# mjGSM.net
KiCad netlist of a schematic drawn in EAGLE
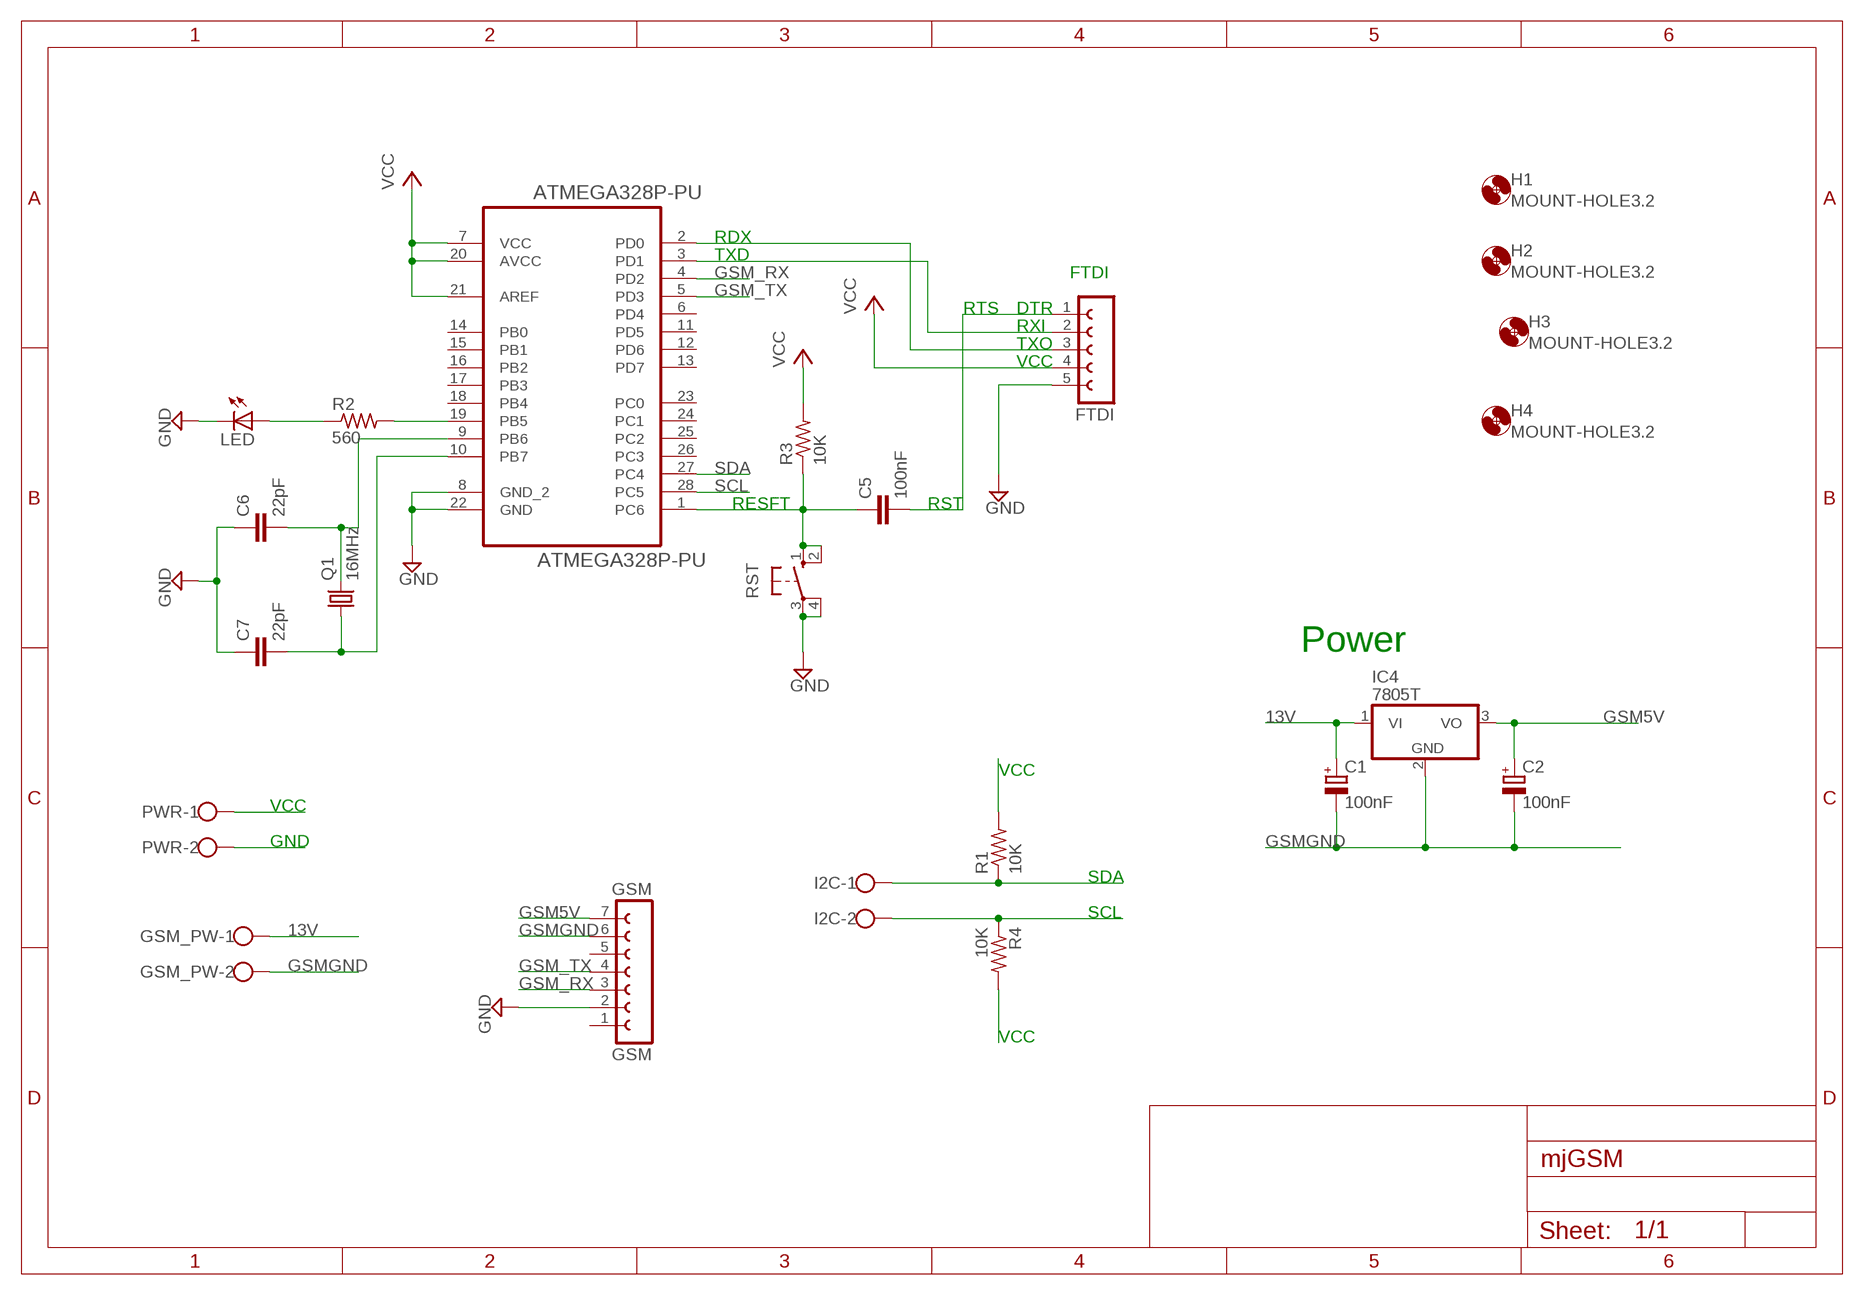
[diagram p0: schematic, sheet 1]

(export (version "E")
  (design (tool "Eeschema 10.0.6"))
  (components
    (comp (ref "ATMEGA328P-PU")
      (value "ATMEGA328P-PU")
      (footprint "eagle-import:DIP254P762X457-28")
      (libsource (lib "eagle-import") (part "ATMEGA328P-PU"))
    )
    (comp (ref "C1")
      (value "100nF")
      (footprint "eagle-import:E2-4")
      (libsource (lib "eagle-import") (part "CPOL-EUE2-4"))
    )
    (comp (ref "C2")
      (value "100nF")
      (footprint "eagle-import:E2-4")
      (libsource (lib "eagle-import") (part "CPOL-EUE2-4"))
    )
    (comp (ref "C5")
      (value "100nF")
      (footprint "eagle-import:C025-024X044")
      (libsource (lib "eagle-import") (part "C-EU025-024X044"))
    )
    (comp (ref "C6")
      (value "22pF")
      (footprint "eagle-import:C025-024X044")
      (libsource (lib "eagle-import") (part "C-EU025-024X044"))
    )
    (comp (ref "C7")
      (value "22pF")
      (footprint "eagle-import:C025-024X044")
      (libsource (lib "eagle-import") (part "C-EU025-024X044"))
    )
    (comp (ref "FTDI")
      (value "FE05-1")
      (footprint "eagle-import:FE05-1")
      (libsource (lib "eagle-import") (part "FE05-1"))
    )
    (comp (ref "GSM")
      (value "GSM")
      (footprint "eagle-import:FE07")
      (libsource (lib "eagle-import") (part "FE07-1"))
    )
    (comp (ref "GSM_PW")
      (value "W237-102")
      (footprint "eagle-import:W237-102")
      (fields (field (name "MPN") "237-102"))
      (libsource (lib "eagle-import") (part "W237-102"))
    )
    (comp (ref "H1")
      (value "MOUNT-HOLE3.2")
      (footprint "eagle-import:3,2")
      (libsource (lib "eagle-import") (part "MOUNT-HOLE3.2"))
    )
    (comp (ref "H2")
      (value "MOUNT-HOLE3.2")
      (footprint "eagle-import:3,2")
      (libsource (lib "eagle-import") (part "MOUNT-HOLE3.2"))
    )
    (comp (ref "H3")
      (value "MOUNT-HOLE3.2")
      (footprint "eagle-import:3,2")
      (libsource (lib "eagle-import") (part "MOUNT-HOLE3.2"))
    )
    (comp (ref "H4")
      (value "MOUNT-HOLE3.2")
      (footprint "eagle-import:3,2")
      (libsource (lib "eagle-import") (part "MOUNT-HOLE3.2"))
    )
    (comp (ref "I2C")
      (value "W237-102")
      (footprint "eagle-import:W237-102")
      (fields (field (name "MPN") "237-102"))
      (libsource (lib "eagle-import") (part "W237-102"))
    )
    (comp (ref "IC4")
      (value "7805T")
      (footprint "eagle-import:TO220H")
      (libsource (lib "eagle-import") (part "78T05"))
    )
    (comp (ref "LED")
      (value "LED3MM")
      (footprint "eagle-import:LED3MM")
      (libsource (lib "eagle-import") (part "LED3MM"))
    )
    (comp (ref "PWR")
      (value "W237-102")
      (footprint "eagle-import:W237-102")
      (fields (field (name "MPN") "237-102") (field (name "SPICEPREFIX") "X"))
      (libsource (lib "eagle-import") (part "W237-102"))
    )
    (comp (ref "Q1")
      (value "16MHz")
      (footprint "eagle-import:HC49_S")
      (libsource (lib "eagle-import") (part "CRYSTALHC49S"))
    )
    (comp (ref "R1")
      (value "10K")
      (footprint "eagle-import:0204_5")
      (libsource (lib "eagle-import") (part "R-US_0204/5"))
    )
    (comp (ref "R2")
      (value "560")
      (footprint "eagle-import:0204_5")
      (libsource (lib "eagle-import") (part "R-US_0204/5"))
    )
    (comp (ref "R3")
      (value "10K")
      (footprint "eagle-import:0204_5")
      (libsource (lib "eagle-import") (part "R-US_0204/5"))
    )
    (comp (ref "R4")
      (value "10K")
      (footprint "eagle-import:0204_5")
      (libsource (lib "eagle-import") (part "R-US_0204/5"))
    )
    (comp (ref "RST")
      (value "10-XX")
      (footprint "eagle-import:B3F-10XX")
      (fields (field (name "MPN") "B3F-1000"))
      (libsource (lib "eagle-import") (part "10-XX"))
    )
  )
  (nets
    (net (code "1") (name "/13V") (class "Default")
      (node (ref "C1") (pin "+") (pinfunction "+_+") (pintype "passive"))
      (node (ref "GSM_PW") (pin "1") (pinfunction "KL_1") (pintype "passive"))
      (node (ref "IC4") (pin "1") (pinfunction "VI_1") (pintype "input"))
    )
    (net (code "2") (name "/GSM5V") (class "Default")
      (node (ref "C2") (pin "+") (pinfunction "+_+") (pintype "passive"))
      (node (ref "GSM") (pin "7") (pinfunction "7_7") (pintype "passive"))
      (node (ref "IC4") (pin "3") (pinfunction "VO_3") (pintype "passive"))
    )
    (net (code "3") (name "/GSMGND") (class "Default")
      (node (ref "C1") (pin "-") (pinfunction "-_-") (pintype "passive"))
      (node (ref "C2") (pin "-") (pinfunction "-_-") (pintype "passive"))
      (node (ref "GSM") (pin "6") (pinfunction "6_6") (pintype "passive"))
      (node (ref "GSM_PW") (pin "2") (pinfunction "KL_2") (pintype "passive"))
      (node (ref "IC4") (pin "2") (pinfunction "GND_2") (pintype "passive"))
    )
    (net (code "4") (name "/GSM_RX") (class "Default")
      (node (ref "ATMEGA328P-PU") (pin "4") (pinfunction "PD2_4") (pintype "bidirectional"))
      (node (ref "GSM") (pin "3") (pinfunction "3_3") (pintype "passive"))
    )
    (net (code "5") (name "/GSM_TX") (class "Default")
      (node (ref "ATMEGA328P-PU") (pin "5") (pinfunction "PD3_5") (pintype "bidirectional"))
      (node (ref "GSM") (pin "4") (pinfunction "4_4") (pintype "passive"))
    )
    (net (code "6") (name "/SCL") (class "Default")
      (node (ref "ATMEGA328P-PU") (pin "28") (pinfunction "PC5_28") (pintype "bidirectional"))
      (node (ref "I2C") (pin "2") (pinfunction "KL_2") (pintype "passive"))
      (node (ref "R4") (pin "1") (pinfunction "1_1") (pintype "passive"))
    )
    (net (code "7") (name "/SDA") (class "Default")
      (node (ref "ATMEGA328P-PU") (pin "27") (pinfunction "PC4_27") (pintype "bidirectional"))
      (node (ref "I2C") (pin "1") (pinfunction "KL_1") (pintype "passive"))
      (node (ref "R1") (pin "1") (pinfunction "1_1") (pintype "passive"))
    )
    (net (code "8") (name "GND") (class "Default")
      (node (ref "ATMEGA328P-PU") (pin "22") (pinfunction "GND_22") (pintype "passive"))
      (node (ref "ATMEGA328P-PU") (pin "8") (pinfunction "GND_2_8") (pintype "passive"))
      (node (ref "C6") (pin "1") (pinfunction "1_1") (pintype "passive"))
      (node (ref "C7") (pin "1") (pinfunction "1_1") (pintype "passive"))
      (node (ref "FTDI") (pin "5") (pinfunction "5_5") (pintype "passive"))
      (node (ref "GSM") (pin "2") (pinfunction "2_2") (pintype "passive"))
      (node (ref "LED") (pin "K") (pinfunction "C_K") (pintype "passive"))
      (node (ref "PWR") (pin "2") (pinfunction "KL_2") (pintype "passive"))
      (node (ref "RST") (pin "3") (pinfunction "P_3") (pintype "passive"))
      (node (ref "RST") (pin "4") (pinfunction "P1_4") (pintype "passive"))
    )
    (net (code "9") (name "Net-(ATMEGA328P-PU-PB5)") (class "Default")
      (node (ref "ATMEGA328P-PU") (pin "19") (pinfunction "PB5_19") (pintype "bidirectional"))
      (node (ref "R2") (pin "2") (pinfunction "2_2") (pintype "passive"))
    )
    (net (code "10") (name "Net-(ATMEGA328P-PU-PB6)") (class "Default")
      (node (ref "ATMEGA328P-PU") (pin "9") (pinfunction "PB6_9") (pintype "bidirectional"))
      (node (ref "C6") (pin "2") (pinfunction "2_2") (pintype "passive"))
      (node (ref "Q1") (pin "2") (pinfunction "2_2") (pintype "passive"))
    )
    (net (code "11") (name "Net-(ATMEGA328P-PU-PB7)") (class "Default")
      (node (ref "ATMEGA328P-PU") (pin "10") (pinfunction "PB7_10") (pintype "bidirectional"))
      (node (ref "C7") (pin "2") (pinfunction "2_2") (pintype "passive"))
      (node (ref "Q1") (pin "1") (pinfunction "1_1") (pintype "passive"))
    )
    (net (code "12") (name "Net-(ATMEGA328P-PU-PC6)") (class "Default")
      (node (ref "ATMEGA328P-PU") (pin "1") (pinfunction "PC6_1") (pintype "bidirectional"))
      (node (ref "C5") (pin "1") (pinfunction "1_1") (pintype "passive"))
      (node (ref "R3") (pin "1") (pinfunction "1_1") (pintype "passive"))
      (node (ref "RST") (pin "1") (pinfunction "S_1") (pintype "passive"))
      (node (ref "RST") (pin "2") (pinfunction "S1_2") (pintype "passive"))
    )
    (net (code "13") (name "Net-(ATMEGA328P-PU-PD0)") (class "Default")
      (node (ref "ATMEGA328P-PU") (pin "2") (pinfunction "PD0_2") (pintype "bidirectional"))
      (node (ref "FTDI") (pin "3") (pinfunction "3_3") (pintype "passive"))
    )
    (net (code "14") (name "Net-(ATMEGA328P-PU-PD1)") (class "Default")
      (node (ref "ATMEGA328P-PU") (pin "3") (pinfunction "PD1_3") (pintype "bidirectional"))
      (node (ref "FTDI") (pin "2") (pinfunction "2_2") (pintype "passive"))
    )
    (net (code "15") (name "Net-(C5-Pad2)") (class "Default")
      (node (ref "C5") (pin "2") (pinfunction "2_2") (pintype "passive"))
      (node (ref "FTDI") (pin "1") (pinfunction "1_1") (pintype "passive"))
    )
    (net (code "16") (name "Net-(LED-PadA)") (class "Default")
      (node (ref "LED") (pin "A") (pinfunction "A_A") (pintype "passive"))
      (node (ref "R2") (pin "1") (pinfunction "1_1") (pintype "passive"))
    )
    (net (code "17") (name "VCC") (class "Default")
      (node (ref "ATMEGA328P-PU") (pin "20") (pinfunction "AVCC_20") (pintype "power_in"))
      (node (ref "ATMEGA328P-PU") (pin "21") (pinfunction "AREF_21") (pintype "input"))
      (node (ref "ATMEGA328P-PU") (pin "7") (pinfunction "VCC_7") (pintype "power_in"))
      (node (ref "FTDI") (pin "4") (pinfunction "4_4") (pintype "passive"))
      (node (ref "PWR") (pin "1") (pinfunction "KL_1") (pintype "passive"))
      (node (ref "R1") (pin "2") (pinfunction "2_2") (pintype "passive"))
      (node (ref "R3") (pin "2") (pinfunction "2_2") (pintype "passive"))
      (node (ref "R4") (pin "2") (pinfunction "2_2") (pintype "passive"))
    )
    (net (code "18") (name "unconnected-(ATMEGA328P-PU-PB0-Pad14)") (class "Default")
      (node (ref "ATMEGA328P-PU") (pin "14") (pinfunction "PB0_14") (pintype "bidirectional"))
    )
    (net (code "19") (name "unconnected-(ATMEGA328P-PU-PB1-Pad15)") (class "Default")
      (node (ref "ATMEGA328P-PU") (pin "15") (pinfunction "PB1_15") (pintype "bidirectional"))
    )
    (net (code "20") (name "unconnected-(ATMEGA328P-PU-PB2-Pad16)") (class "Default")
      (node (ref "ATMEGA328P-PU") (pin "16") (pinfunction "PB2_16") (pintype "bidirectional"))
    )
    (net (code "21") (name "unconnected-(ATMEGA328P-PU-PB3-Pad17)") (class "Default")
      (node (ref "ATMEGA328P-PU") (pin "17") (pinfunction "PB3_17") (pintype "bidirectional"))
    )
    (net (code "22") (name "unconnected-(ATMEGA328P-PU-PB4-Pad18)") (class "Default")
      (node (ref "ATMEGA328P-PU") (pin "18") (pinfunction "PB4_18") (pintype "bidirectional"))
    )
    (net (code "23") (name "unconnected-(ATMEGA328P-PU-PC0-Pad23)") (class "Default")
      (node (ref "ATMEGA328P-PU") (pin "23") (pinfunction "PC0_23") (pintype "bidirectional"))
    )
    (net (code "24") (name "unconnected-(ATMEGA328P-PU-PC1-Pad24)") (class "Default")
      (node (ref "ATMEGA328P-PU") (pin "24") (pinfunction "PC1_24") (pintype "bidirectional"))
    )
    (net (code "25") (name "unconnected-(ATMEGA328P-PU-PC2-Pad25)") (class "Default")
      (node (ref "ATMEGA328P-PU") (pin "25") (pinfunction "PC2_25") (pintype "bidirectional"))
    )
    (net (code "26") (name "unconnected-(ATMEGA328P-PU-PC3-Pad26)") (class "Default")
      (node (ref "ATMEGA328P-PU") (pin "26") (pinfunction "PC3_26") (pintype "bidirectional"))
    )
    (net (code "27") (name "unconnected-(ATMEGA328P-PU-PD4-Pad6)") (class "Default")
      (node (ref "ATMEGA328P-PU") (pin "6") (pinfunction "PD4_6") (pintype "bidirectional"))
    )
    (net (code "28") (name "unconnected-(ATMEGA328P-PU-PD5-Pad11)") (class "Default")
      (node (ref "ATMEGA328P-PU") (pin "11") (pinfunction "PD5_11") (pintype "bidirectional"))
    )
    (net (code "29") (name "unconnected-(ATMEGA328P-PU-PD6-Pad12)") (class "Default")
      (node (ref "ATMEGA328P-PU") (pin "12") (pinfunction "PD6_12") (pintype "bidirectional"))
    )
    (net (code "30") (name "unconnected-(ATMEGA328P-PU-PD7-Pad13)") (class "Default")
      (node (ref "ATMEGA328P-PU") (pin "13") (pinfunction "PD7_13") (pintype "bidirectional"))
    )
    (net (code "31") (name "unconnected-(GSM-Pad1)") (class "Default")
      (node (ref "GSM") (pin "1") (pinfunction "1_1") (pintype "passive"))
    )
    (net (code "32") (name "unconnected-(GSM-Pad5)") (class "Default")
      (node (ref "GSM") (pin "5") (pinfunction "5_5") (pintype "passive"))
    )
  )
)
